# ADS1015_shield.net
KiCad netlist of a schematic drawn in Altium Designer
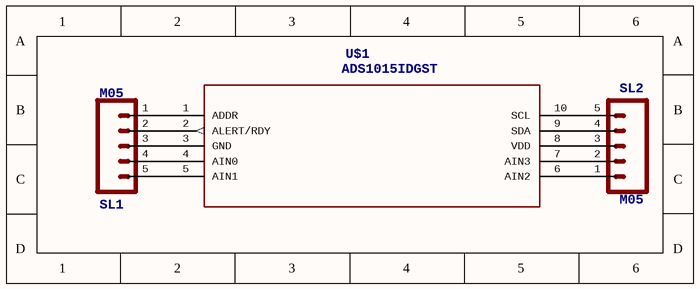
[diagram p0: ADS1015_shield.SchDoc]

(export (version "E")
  (design (tool "Eeschema 10.0.6"))
  (components
    (comp (ref "SL1")
      (value "M05")
      (footprint "05P")
      (description "<b>AMP QUICK CONNECTOR</b>")
      (libsource (lib "con-amp-quick") (part "M05"))
    )
    (comp (ref "SL2")
      (value "M05")
      (footprint "05P")
      (description "<b>AMP QUICK CONNECTOR</b>")
      (libsource (lib "con-amp-quick") (part "M05"))
    )
    (comp (ref "U$1")
      (value "ADS1015IDGST")
      (footprint "DGS10")
      (fields
        (field (name "RSPARTNUMBER") "7094550")
        (field (name "COPYRIGHT") "Copyright C 2015 Accelerated Designs. All rights reserved")
      )
      (libsource (lib "ADS105IDGST") (part "ADS1015IDGST"))
    )
  )
  (nets
    (net (code "1") (name "Net-(U$1-ADDR)") (class "Default")
      (node (ref "SL1") (pin "1") (pinfunction "1_1") (pintype "passive"))
      (node (ref "U$1") (pin "1") (pinfunction "ADDR_1") (pintype "passive"))
    )
    (net (code "2") (name "Net-(U$1-AIN0)") (class "Default")
      (node (ref "SL1") (pin "4") (pinfunction "4_4") (pintype "passive"))
      (node (ref "U$1") (pin "4") (pinfunction "AIN0_4") (pintype "passive"))
    )
    (net (code "3") (name "Net-(U$1-AIN1)") (class "Default")
      (node (ref "SL1") (pin "5") (pinfunction "5_5") (pintype "passive"))
      (node (ref "U$1") (pin "5") (pinfunction "AIN1_5") (pintype "passive"))
    )
    (net (code "4") (name "Net-(U$1-AIN2)") (class "Default")
      (node (ref "SL2") (pin "1") (pinfunction "1_1") (pintype "passive"))
      (node (ref "U$1") (pin "6") (pinfunction "AIN2_6") (pintype "passive"))
    )
    (net (code "5") (name "Net-(U$1-AIN3)") (class "Default")
      (node (ref "SL2") (pin "2") (pinfunction "2_2") (pintype "passive"))
      (node (ref "U$1") (pin "7") (pinfunction "AIN3_7") (pintype "passive"))
    )
    (net (code "6") (name "Net-(U$1-ALERT{slash}RDY)") (class "Default")
      (node (ref "SL1") (pin "2") (pinfunction "2_2") (pintype "passive"))
      (node (ref "U$1") (pin "2") (pinfunction "ALERT/RDY_2") (pintype "output"))
    )
    (net (code "7") (name "Net-(U$1-GND)") (class "Default")
      (node (ref "SL1") (pin "3") (pinfunction "3_3") (pintype "passive"))
      (node (ref "U$1") (pin "3") (pinfunction "GND_3") (pintype "power_in"))
    )
    (net (code "8") (name "Net-(U$1-SCL)") (class "Default")
      (node (ref "SL2") (pin "5") (pinfunction "5_5") (pintype "passive"))
      (node (ref "U$1") (pin "10") (pinfunction "SCL_10") (pintype "passive"))
    )
    (net (code "9") (name "Net-(U$1-SDA)") (class "Default")
      (node (ref "SL2") (pin "4") (pinfunction "4_4") (pintype "passive"))
      (node (ref "U$1") (pin "9") (pinfunction "SDA_9") (pintype "passive"))
    )
    (net (code "10") (name "Net-(U$1-VDD)") (class "Default")
      (node (ref "SL2") (pin "3") (pinfunction "3_3") (pintype "passive"))
      (node (ref "U$1") (pin "8") (pinfunction "VDD_8") (pintype "power_in"))
    )
  )
)
